# MCU.net
KiCad netlist of a schematic drawn in Altium Designer
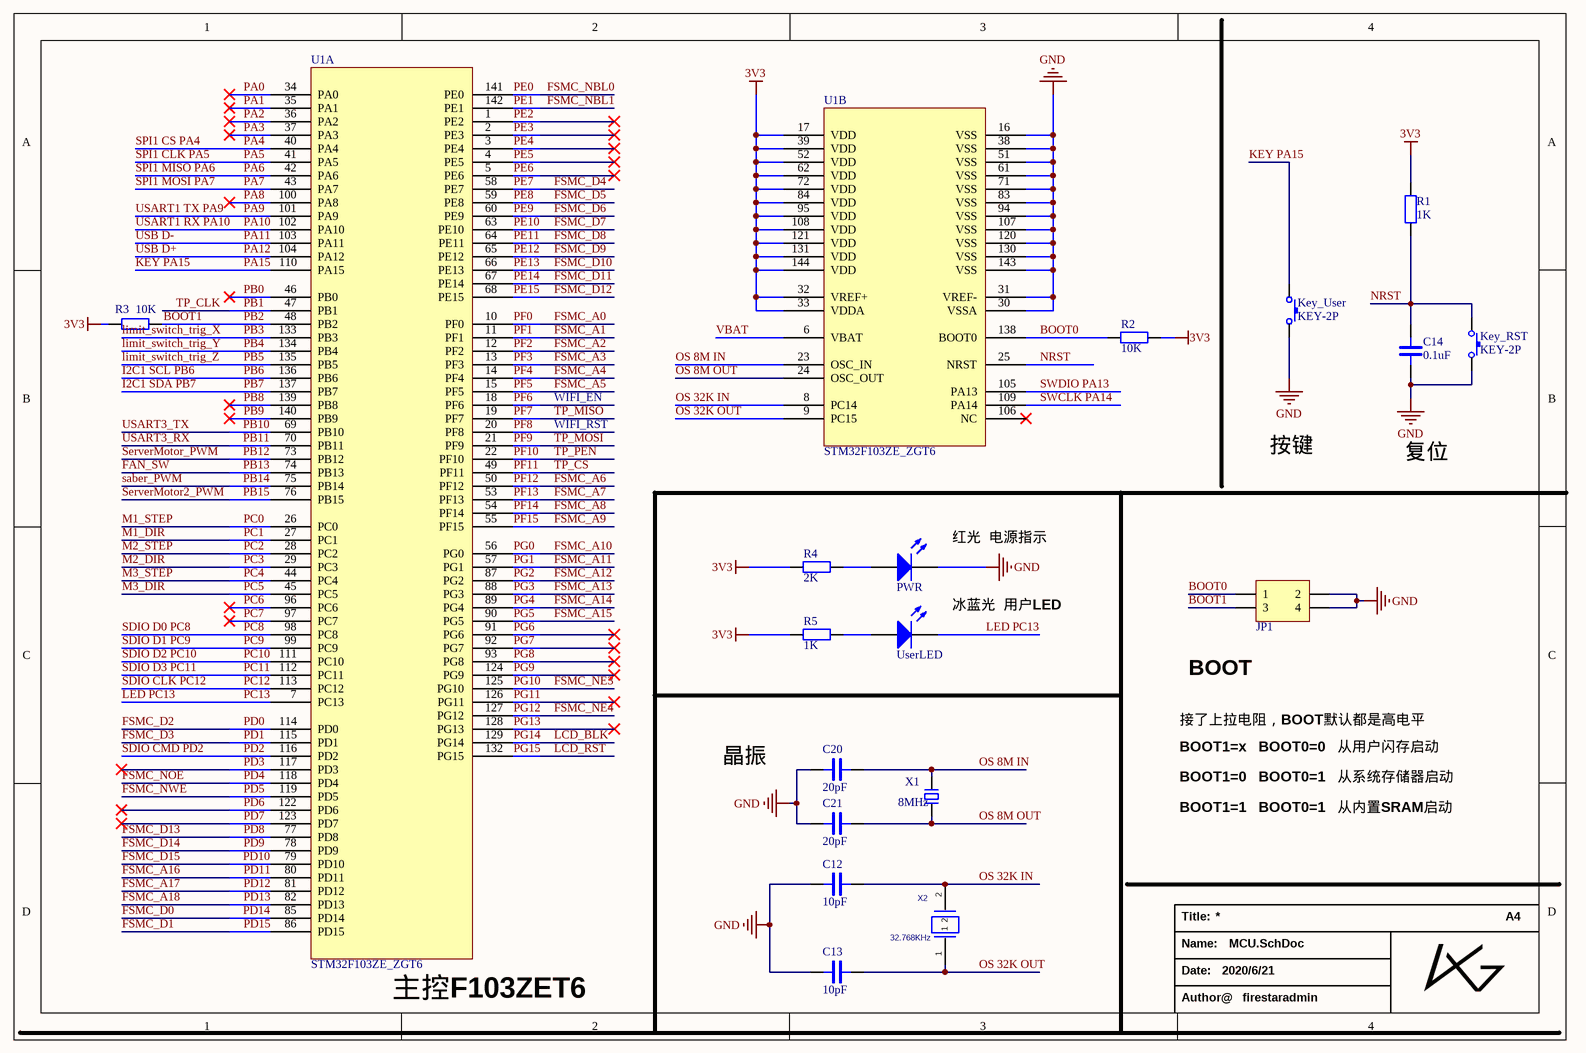
[diagram p0: MCU.SchDoc]

(export (version "E")
  (design (tool "Eeschema 10.0.6"))
  (components
    (comp (ref "C12")
      (value "10pF")
      (footprint "C 0603_M")
      (description "Capacitor")
      (libsource (lib "General") (part "CAP"))
    )
    (comp (ref "C13")
      (value "10pF")
      (footprint "C 0603_M")
      (description "Capacitor")
      (libsource (lib "General") (part "CAP"))
    )
    (comp (ref "C14")
      (value "0.1uF")
      (footprint "C 0603_M")
      (description "Capacitor")
      (libsource (lib "General") (part "CAP"))
    )
    (comp (ref "C20")
      (value "20pF")
      (footprint "C 0603_M")
      (description "Capacitor")
      (libsource (lib "General") (part "CAP"))
    )
    (comp (ref "C21")
      (value "20pF")
      (footprint "C 0603_M")
      (description "Capacitor")
      (libsource (lib "General") (part "CAP"))
    )
    (comp (ref "JP1")
      (value "Header2X2")
      (footprint "HDR2.54-LI-2x2P")
      (description "2*2P接插件")
      (fields (field (name "版权归属") "源创客"))
      (libsource (lib "4.5   - 接插件-脚距2.54") (part "Header 2X2"))
    )
    (comp (ref "Key_RST")
      (value "KEY-2P")
      (footprint "TSW SMD-3*6*2.5")
      (description "Key")
      (libsource (lib "General") (part "KEY-2P"))
    )
    (comp (ref "Key_User")
      (value "KEY-2P")
      (footprint "TSW SMD-3*6*2.5")
      (description "Key")
      (libsource (lib "General") (part "KEY-2P"))
    )
    (comp (ref "PWR")
      (value "LED")
      (footprint "LED 0603R")
      (libsource (lib "altium-import") (part "root_0_LED_"))
    )
    (comp (ref "R1")
      (value "1K")
      (footprint "R 0603_M")
      (description "Resistor")
      (libsource (lib "") (part "RES_1"))
    )
    (comp (ref "R2")
      (value "10K")
      (footprint "R 0603_M")
      (description "Resistor")
      (libsource (lib "") (part "RES_2"))
    )
    (comp (ref "R3")
      (value "10K")
      (footprint "R 0603_M")
      (description "Resistor")
      (libsource (lib "General") (part "RES"))
    )
    (comp (ref "R4")
      (value "2K")
      (footprint "R 0603_M")
      (description "Resistor")
      (libsource (lib "General") (part "RES"))
    )
    (comp (ref "R5")
      (value "1K")
      (footprint "R 0603_M")
      (description "Resistor")
      (libsource (lib "General") (part "RES"))
    )
    (comp (ref "U1")
      (value "STM32F103ZE_ZGT6")
      (footprint "TQFP144 20x20_M")
      (libsource (lib "altium-import") (part "root_0_STM32F103ZE_ZGT6_"))
    )
    (comp (ref "UserLED")
      (value "LED")
      (footprint "LED 0603B")
      (libsource (lib "altium-import") (part "root_0_LED_"))
    )
    (comp (ref "X1")
      (value "8MHz")
      (footprint "OSC 5032-2P")
      (description "2脚无源脚晶振")
      (fields (field (name "版权归属") "源创客"))
      (libsource (lib "10.1 - 保险丝-晶振") (part "XTAL-2P"))
    )
    (comp (ref "X2")
      (value "32.768KHz")
      (footprint "OSC 3215-2P")
      (description "CRYSTAL")
      (fields (field (name "Comment") "XTAL_32.768KHZ_3215"))
      (libsource (lib "altium-import") (part "root_0_XTAL_32.768KHZ_3215_"))
    )
  )
  (nets
    (net (code "1") (name "/BOOT0") (class "Default")
      (node (ref "JP1") (pin "1") (pinfunction "1_1") (pintype "passive"))
      (node (ref "R2") (pin "1") (pinfunction "1_1") (pintype "passive"))
      (node (ref "U1") (pin "138") (pinfunction "BOOT0_138") (pintype "passive"))
    )
    (net (code "2") (name "/BOOT1") (class "Default")
      (node (ref "JP1") (pin "3") (pinfunction "3_3") (pintype "passive"))
      (node (ref "R3") (pin "1") (pinfunction "1_1") (pintype "passive"))
      (node (ref "U1") (pin "48") (pinfunction "PB2_48") (pintype "passive"))
    )
    (net (code "3") (name "/FAN_SW") (class "Default")
      (node (ref "U1") (pin "74") (pinfunction "PB13_74") (pintype "passive"))
    )
    (net (code "4") (name "/FSMC_A0") (class "Default")
      (node (ref "U1") (pin "10") (pinfunction "PF0_10") (pintype "passive"))
    )
    (net (code "5") (name "/FSMC_A1") (class "Default")
      (node (ref "U1") (pin "11") (pinfunction "PF1_11") (pintype "passive"))
    )
    (net (code "6") (name "/FSMC_A2") (class "Default")
      (node (ref "U1") (pin "12") (pinfunction "PF2_12") (pintype "passive"))
    )
    (net (code "7") (name "/FSMC_A3") (class "Default")
      (node (ref "U1") (pin "13") (pinfunction "PF3_13") (pintype "passive"))
    )
    (net (code "8") (name "/FSMC_A4") (class "Default")
      (node (ref "U1") (pin "14") (pinfunction "PF4_14") (pintype "passive"))
    )
    (net (code "9") (name "/FSMC_A5") (class "Default")
      (node (ref "U1") (pin "15") (pinfunction "PF5_15") (pintype "passive"))
    )
    (net (code "10") (name "/FSMC_A6") (class "Default")
      (node (ref "U1") (pin "50") (pinfunction "PF12_50") (pintype "passive"))
    )
    (net (code "11") (name "/FSMC_A7") (class "Default")
      (node (ref "U1") (pin "53") (pinfunction "PF13_53") (pintype "passive"))
    )
    (net (code "12") (name "/FSMC_A8") (class "Default")
      (node (ref "U1") (pin "54") (pinfunction "PF14_54") (pintype "passive"))
    )
    (net (code "13") (name "/FSMC_A9") (class "Default")
      (node (ref "U1") (pin "55") (pinfunction "PF15_55") (pintype "passive"))
    )
    (net (code "14") (name "/FSMC_A10") (class "Default")
      (node (ref "U1") (pin "56") (pinfunction "PG0_56") (pintype "passive"))
    )
    (net (code "15") (name "/FSMC_A11") (class "Default")
      (node (ref "U1") (pin "57") (pinfunction "PG1_57") (pintype "passive"))
    )
    (net (code "16") (name "/FSMC_A12") (class "Default")
      (node (ref "U1") (pin "87") (pinfunction "PG2_87") (pintype "passive"))
    )
    (net (code "17") (name "/FSMC_A13") (class "Default")
      (node (ref "U1") (pin "88") (pinfunction "PG3_88") (pintype "passive"))
    )
    (net (code "18") (name "/FSMC_A14") (class "Default")
      (node (ref "U1") (pin "89") (pinfunction "PG4_89") (pintype "passive"))
    )
    (net (code "19") (name "/FSMC_A15") (class "Default")
      (node (ref "U1") (pin "90") (pinfunction "PG5_90") (pintype "passive"))
    )
    (net (code "20") (name "/FSMC_A16") (class "Default")
      (node (ref "U1") (pin "80") (pinfunction "PD11_80") (pintype "passive"))
    )
    (net (code "21") (name "/FSMC_A17") (class "Default")
      (node (ref "U1") (pin "81") (pinfunction "PD12_81") (pintype "passive"))
    )
    (net (code "22") (name "/FSMC_A18") (class "Default")
      (node (ref "U1") (pin "82") (pinfunction "PD13_82") (pintype "passive"))
    )
    (net (code "23") (name "/FSMC_D0") (class "Default")
      (node (ref "U1") (pin "85") (pinfunction "PD14_85") (pintype "passive"))
    )
    (net (code "24") (name "/FSMC_D1") (class "Default")
      (node (ref "U1") (pin "86") (pinfunction "PD15_86") (pintype "passive"))
    )
    (net (code "25") (name "/FSMC_D2") (class "Default")
      (node (ref "U1") (pin "114") (pinfunction "PD0_114") (pintype "passive"))
    )
    (net (code "26") (name "/FSMC_D3") (class "Default")
      (node (ref "U1") (pin "115") (pinfunction "PD1_115") (pintype "passive"))
    )
    (net (code "27") (name "/FSMC_D4") (class "Default")
      (node (ref "U1") (pin "58") (pinfunction "PE7_58") (pintype "passive"))
    )
    (net (code "28") (name "/FSMC_D5") (class "Default")
      (node (ref "U1") (pin "59") (pinfunction "PE8_59") (pintype "passive"))
    )
    (net (code "29") (name "/FSMC_D6") (class "Default")
      (node (ref "U1") (pin "60") (pinfunction "PE9_60") (pintype "passive"))
    )
    (net (code "30") (name "/FSMC_D7") (class "Default")
      (node (ref "U1") (pin "63") (pinfunction "PE10_63") (pintype "passive"))
    )
    (net (code "31") (name "/FSMC_D8") (class "Default")
      (node (ref "U1") (pin "64") (pinfunction "PE11_64") (pintype "passive"))
    )
    (net (code "32") (name "/FSMC_D9") (class "Default")
      (node (ref "U1") (pin "65") (pinfunction "PE12_65") (pintype "passive"))
    )
    (net (code "33") (name "/FSMC_D10") (class "Default")
      (node (ref "U1") (pin "66") (pinfunction "PE13_66") (pintype "passive"))
    )
    (net (code "34") (name "/FSMC_D11") (class "Default")
      (node (ref "U1") (pin "67") (pinfunction "PE14_67") (pintype "passive"))
    )
    (net (code "35") (name "/FSMC_D12") (class "Default")
      (node (ref "U1") (pin "68") (pinfunction "PE15_68") (pintype "passive"))
    )
    (net (code "36") (name "/FSMC_D13") (class "Default")
      (node (ref "U1") (pin "77") (pinfunction "PD8_77") (pintype "passive"))
    )
    (net (code "37") (name "/FSMC_D14") (class "Default")
      (node (ref "U1") (pin "78") (pinfunction "PD9_78") (pintype "passive"))
    )
    (net (code "38") (name "/FSMC_D15") (class "Default")
      (node (ref "U1") (pin "79") (pinfunction "PD10_79") (pintype "passive"))
    )
    (net (code "39") (name "/FSMC_NBL0") (class "Default")
      (node (ref "U1") (pin "141") (pinfunction "PE0_141") (pintype "passive"))
    )
    (net (code "40") (name "/FSMC_NBL1") (class "Default")
      (node (ref "U1") (pin "142") (pinfunction "PE1_142") (pintype "passive"))
    )
    (net (code "41") (name "/FSMC_NE3") (class "Default")
      (node (ref "U1") (pin "125") (pinfunction "PG10_125") (pintype "passive"))
    )
    (net (code "42") (name "/FSMC_NE4") (class "Default")
      (node (ref "U1") (pin "127") (pinfunction "PG12_127") (pintype "passive"))
    )
    (net (code "43") (name "/FSMC_NOE") (class "Default")
      (node (ref "U1") (pin "118") (pinfunction "PD4_118") (pintype "passive"))
    )
    (net (code "44") (name "/FSMC_NWE") (class "Default")
      (node (ref "U1") (pin "119") (pinfunction "PD5_119") (pintype "passive"))
    )
    (net (code "45") (name "/I2C1 SCL PB6") (class "Default")
      (node (ref "U1") (pin "136") (pinfunction "PB6_136") (pintype "passive"))
    )
    (net (code "46") (name "/I2C1 SDA PB7") (class "Default")
      (node (ref "U1") (pin "137") (pinfunction "PB7_137") (pintype "passive"))
    )
    (net (code "47") (name "/KEY PA15") (class "Default")
      (node (ref "Key_User") (pin "1") (pinfunction "1_1") (pintype "passive"))
      (node (ref "U1") (pin "110") (pinfunction "PA15_110") (pintype "passive"))
    )
    (net (code "48") (name "/LCD_BLK") (class "Default")
      (node (ref "U1") (pin "129") (pinfunction "PG14_129") (pintype "passive"))
    )
    (net (code "49") (name "/LCD_RST") (class "Default")
      (node (ref "U1") (pin "132") (pinfunction "PG15_132") (pintype "passive"))
    )
    (net (code "50") (name "/LED PC13") (class "Default")
      (node (ref "U1") (pin "7") (pinfunction "PC13_7") (pintype "passive"))
      (node (ref "UserLED") (pin "2") (pinfunction "K_2") (pintype "passive"))
    )
    (net (code "51") (name "/M1_DIR") (class "Default")
      (node (ref "U1") (pin "27") (pinfunction "PC1_27") (pintype "passive"))
    )
    (net (code "52") (name "/M1_STEP") (class "Default")
      (node (ref "U1") (pin "26") (pinfunction "PC0_26") (pintype "passive"))
    )
    (net (code "53") (name "/M2_DIR") (class "Default")
      (node (ref "U1") (pin "29") (pinfunction "PC3_29") (pintype "passive"))
    )
    (net (code "54") (name "/M2_STEP") (class "Default")
      (node (ref "U1") (pin "28") (pinfunction "PC2_28") (pintype "passive"))
    )
    (net (code "55") (name "/M3_DIR") (class "Default")
      (node (ref "U1") (pin "45") (pinfunction "PC5_45") (pintype "passive"))
    )
    (net (code "56") (name "/M3_STEP") (class "Default")
      (node (ref "U1") (pin "44") (pinfunction "PC4_44") (pintype "passive"))
    )
    (net (code "57") (name "/NRST") (class "Default")
      (node (ref "C14") (pin "2") (pinfunction "2_2") (pintype "passive"))
      (node (ref "Key_RST") (pin "1") (pinfunction "1_1") (pintype "passive"))
      (node (ref "R1") (pin "2") (pinfunction "2_2") (pintype "passive"))
      (node (ref "U1") (pin "25") (pinfunction "NRST_25") (pintype "passive"))
    )
    (net (code "58") (name "/OS 8M IN") (class "Default")
      (node (ref "C20") (pin "1") (pinfunction "1_1") (pintype "passive"))
      (node (ref "U1") (pin "23") (pinfunction "OSC_IN_23") (pintype "passive"))
      (node (ref "X1") (pin "1") (pinfunction "1_1") (pintype "passive"))
    )
    (net (code "59") (name "/OS 8M OUT") (class "Default")
      (node (ref "C21") (pin "1") (pinfunction "1_1") (pintype "passive"))
      (node (ref "U1") (pin "24") (pinfunction "OSC_OUT_24") (pintype "passive"))
      (node (ref "X1") (pin "2") (pinfunction "2_2") (pintype "passive"))
    )
    (net (code "60") (name "/OS 32K IN") (class "Default")
      (node (ref "C12") (pin "1") (pinfunction "1_1") (pintype "passive"))
      (node (ref "U1") (pin "8") (pinfunction "PC14_8") (pintype "passive"))
      (node (ref "X2") (pin "2") (pinfunction "2_2") (pintype "passive"))
    )
    (net (code "61") (name "/OS 32K OUT") (class "Default")
      (node (ref "C13") (pin "1") (pinfunction "1_1") (pintype "passive"))
      (node (ref "U1") (pin "9") (pinfunction "PC15_9") (pintype "passive"))
      (node (ref "X2") (pin "1") (pinfunction "1_1") (pintype "passive"))
    )
    (net (code "62") (name "/PA0") (class "Default")
      (node (ref "U1") (pin "34") (pinfunction "PA0_34") (pintype "passive+no_connect"))
    )
    (net (code "63") (name "/PA1") (class "Default")
      (node (ref "U1") (pin "35") (pinfunction "PA1_35") (pintype "passive+no_connect"))
    )
    (net (code "64") (name "/PA2") (class "Default")
      (node (ref "U1") (pin "36") (pinfunction "PA2_36") (pintype "passive+no_connect"))
    )
    (net (code "65") (name "/PA3") (class "Default")
      (node (ref "U1") (pin "37") (pinfunction "PA3_37") (pintype "passive+no_connect"))
    )
    (net (code "66") (name "/PA4") (class "Default")
      (node (ref "U1") (pin "40") (pinfunction "PA4_40") (pintype "passive"))
    )
    (net (code "67") (name "/PA5") (class "Default")
      (node (ref "U1") (pin "41") (pinfunction "PA5_41") (pintype "passive"))
    )
    (net (code "68") (name "/PA6") (class "Default")
      (node (ref "U1") (pin "42") (pinfunction "PA6_42") (pintype "passive"))
    )
    (net (code "69") (name "/PA7") (class "Default")
      (node (ref "U1") (pin "43") (pinfunction "PA7_43") (pintype "passive"))
    )
    (net (code "70") (name "/PA8") (class "Default")
      (node (ref "U1") (pin "100") (pinfunction "PA8_100") (pintype "passive+no_connect"))
    )
    (net (code "71") (name "/PA9") (class "Default")
      (node (ref "U1") (pin "101") (pinfunction "PA9_101") (pintype "passive"))
    )
    (net (code "72") (name "/PA10") (class "Default")
      (node (ref "U1") (pin "102") (pinfunction "PA10_102") (pintype "passive"))
    )
    (net (code "73") (name "/PA11") (class "Default")
      (node (ref "U1") (pin "103") (pinfunction "PA11_103") (pintype "passive"))
    )
    (net (code "74") (name "/PA12") (class "Default")
      (node (ref "U1") (pin "104") (pinfunction "PA12_104") (pintype "passive"))
    )
    (net (code "75") (name "/PB0") (class "Default")
      (node (ref "U1") (pin "46") (pinfunction "PB0_46") (pintype "passive+no_connect"))
    )
    (net (code "76") (name "/PB1") (class "Default")
      (node (ref "U1") (pin "47") (pinfunction "PB1_47") (pintype "passive"))
    )
    (net (code "77") (name "/PB3") (class "Default")
      (node (ref "U1") (pin "133") (pinfunction "PB3_133") (pintype "passive"))
    )
    (net (code "78") (name "/PB4") (class "Default")
      (node (ref "U1") (pin "134") (pinfunction "PB4_134") (pintype "passive"))
    )
    (net (code "79") (name "/PB5") (class "Default")
      (node (ref "U1") (pin "135") (pinfunction "PB5_135") (pintype "passive"))
    )
    (net (code "80") (name "/PB8") (class "Default")
      (node (ref "U1") (pin "139") (pinfunction "PB8_139") (pintype "passive+no_connect"))
    )
    (net (code "81") (name "/PB9") (class "Default")
      (node (ref "U1") (pin "140") (pinfunction "PB9_140") (pintype "passive+no_connect"))
    )
    (net (code "82") (name "/PB10") (class "Default")
      (node (ref "U1") (pin "69") (pinfunction "PB10_69") (pintype "passive"))
    )
    (net (code "83") (name "/PB11") (class "Default")
      (node (ref "U1") (pin "70") (pinfunction "PB11_70") (pintype "passive"))
    )
    (net (code "84") (name "/PB12") (class "Default")
      (node (ref "U1") (pin "73") (pinfunction "PB12_73") (pintype "passive"))
    )
    (net (code "85") (name "/PB14") (class "Default")
      (node (ref "U1") (pin "75") (pinfunction "PB14_75") (pintype "passive"))
    )
    (net (code "86") (name "/PB15") (class "Default")
      (node (ref "U1") (pin "76") (pinfunction "PB15_76") (pintype "passive"))
    )
    (net (code "87") (name "/PC6") (class "Default")
      (node (ref "U1") (pin "96") (pinfunction "PC6_96") (pintype "passive+no_connect"))
    )
    (net (code "88") (name "/PC7") (class "Default")
      (node (ref "U1") (pin "97") (pinfunction "PC7_97") (pintype "passive+no_connect"))
    )
    (net (code "89") (name "/PC8") (class "Default")
      (node (ref "U1") (pin "98") (pinfunction "PC8_98") (pintype "passive"))
    )
    (net (code "90") (name "/PC9") (class "Default")
      (node (ref "U1") (pin "99") (pinfunction "PC9_99") (pintype "passive"))
    )
    (net (code "91") (name "/PC10") (class "Default")
      (node (ref "U1") (pin "111") (pinfunction "PC10_111") (pintype "passive"))
    )
    (net (code "92") (name "/PC11") (class "Default")
      (node (ref "U1") (pin "112") (pinfunction "PC11_112") (pintype "passive"))
    )
    (net (code "93") (name "/PC12") (class "Default")
      (node (ref "U1") (pin "113") (pinfunction "PC12_113") (pintype "passive"))
    )
    (net (code "94") (name "/PD2") (class "Default")
      (node (ref "U1") (pin "116") (pinfunction "PD2_116") (pintype "passive"))
    )
    (net (code "95") (name "/PD3") (class "Default")
      (node (ref "U1") (pin "117") (pinfunction "PD3_117") (pintype "passive+no_connect"))
    )
    (net (code "96") (name "/PD6") (class "Default")
      (node (ref "U1") (pin "122") (pinfunction "PD6_122") (pintype "passive+no_connect"))
    )
    (net (code "97") (name "/PD7") (class "Default")
      (node (ref "U1") (pin "123") (pinfunction "PD7_123") (pintype "passive+no_connect"))
    )
    (net (code "98") (name "/PE2") (class "Default")
      (node (ref "U1") (pin "1") (pinfunction "PE2_1") (pintype "passive+no_connect"))
    )
    (net (code "99") (name "/PE3") (class "Default")
      (node (ref "U1") (pin "2") (pinfunction "PE3_2") (pintype "passive+no_connect"))
    )
    (net (code "100") (name "/PE4") (class "Default")
      (node (ref "U1") (pin "3") (pinfunction "PE4_3") (pintype "passive+no_connect"))
    )
    (net (code "101") (name "/PE5") (class "Default")
      (node (ref "U1") (pin "4") (pinfunction "PE5_4") (pintype "passive+no_connect"))
    )
    (net (code "102") (name "/PE6") (class "Default")
      (node (ref "U1") (pin "5") (pinfunction "PE6_5") (pintype "passive+no_connect"))
    )
    (net (code "103") (name "/PF6") (class "Default")
      (node (ref "U1") (pin "18") (pinfunction "PF6_18") (pintype "passive"))
    )
    (net (code "104") (name "/PF7") (class "Default")
      (node (ref "U1") (pin "19") (pinfunction "PF7_19") (pintype "passive"))
    )
    (net (code "105") (name "/PF8") (class "Default")
      (node (ref "U1") (pin "20") (pinfunction "PF8_20") (pintype "passive"))
    )
    (net (code "106") (name "/PF9") (class "Default")
      (node (ref "U1") (pin "21") (pinfunction "PF9_21") (pintype "passive"))
    )
    (net (code "107") (name "/PF10") (class "Default")
      (node (ref "U1") (pin "22") (pinfunction "PF10_22") (pintype "passive"))
    )
    (net (code "108") (name "/PF11") (class "Default")
      (node (ref "U1") (pin "49") (pinfunction "PF11_49") (pintype "passive"))
    )
    (net (code "109") (name "/PG6") (class "Default")
      (node (ref "U1") (pin "91") (pinfunction "PG6_91") (pintype "passive+no_connect"))
    )
    (net (code "110") (name "/PG7") (class "Default")
      (node (ref "U1") (pin "92") (pinfunction "PG7_92") (pintype "passive+no_connect"))
    )
    (net (code "111") (name "/PG8") (class "Default")
      (node (ref "U1") (pin "93") (pinfunction "PG8_93") (pintype "passive+no_connect"))
    )
    (net (code "112") (name "/PG9") (class "Default")
      (node (ref "U1") (pin "124") (pinfunction "PG9_124") (pintype "passive+no_connect"))
    )
    (net (code "113") (name "/PG11") (class "Default")
      (node (ref "U1") (pin "126") (pinfunction "PG11_126") (pintype "passive+no_connect"))
    )
    (net (code "114") (name "/PG13") (class "Default")
      (node (ref "U1") (pin "128") (pinfunction "PG13_128") (pintype "passive+no_connect"))
    )
    (net (code "115") (name "/SWCLK PA14") (class "Default")
      (node (ref "U1") (pin "109") (pinfunction "PA14_109") (pintype "passive"))
    )
    (net (code "116") (name "/SWDIO PA13") (class "Default")
      (node (ref "U1") (pin "105") (pinfunction "PA13_105") (pintype "passive"))
    )
    (net (code "117") (name "/VBAT") (class "Default")
      (node (ref "U1") (pin "6") (pinfunction "VBAT_6") (pintype "passive"))
    )
    (net (code "118") (name "3V3") (class "Default")
      (node (ref "R1") (pin "1") (pinfunction "1_1") (pintype "passive"))
      (node (ref "R2") (pin "2") (pinfunction "2_2") (pintype "passive"))
      (node (ref "R3") (pin "2") (pinfunction "2_2") (pintype "passive"))
      (node (ref "R4") (pin "2") (pinfunction "2_2") (pintype "passive"))
      (node (ref "R5") (pin "2") (pinfunction "2_2") (pintype "passive"))
      (node (ref "U1") (pin "108") (pinfunction "VDD_108") (pintype "passive"))
      (node (ref "U1") (pin "121") (pinfunction "VDD_121") (pintype "passive"))
      (node (ref "U1") (pin "131") (pinfunction "VDD_131") (pintype "passive"))
      (node (ref "U1") (pin "144") (pinfunction "VDD_144") (pintype "passive"))
      (node (ref "U1") (pin "17") (pinfunction "VDD_17") (pintype "passive"))
      (node (ref "U1") (pin "32") (pinfunction "VREF+_32") (pintype "passive"))
      (node (ref "U1") (pin "33") (pinfunction "VDDA_33") (pintype "passive"))
      (node (ref "U1") (pin "39") (pinfunction "VDD_39") (pintype "passive"))
      (node (ref "U1") (pin "52") (pinfunction "VDD_52") (pintype "passive"))
      (node (ref "U1") (pin "62") (pinfunction "VDD_62") (pintype "passive"))
      (node (ref "U1") (pin "72") (pinfunction "VDD_72") (pintype "passive"))
      (node (ref "U1") (pin "84") (pinfunction "VDD_84") (pintype "passive"))
      (node (ref "U1") (pin "95") (pinfunction "VDD_95") (pintype "passive"))
    )
    (net (code "119") (name "GND") (class "Default")
      (node (ref "C12") (pin "2") (pinfunction "2_2") (pintype "passive"))
      (node (ref "C13") (pin "2") (pinfunction "2_2") (pintype "passive"))
      (node (ref "C14") (pin "1") (pinfunction "1_1") (pintype "passive"))
      (node (ref "C20") (pin "2") (pinfunction "2_2") (pintype "passive"))
      (node (ref "C21") (pin "2") (pinfunction "2_2") (pintype "passive"))
      (node (ref "JP1") (pin "2") (pinfunction "2_2") (pintype "passive"))
      (node (ref "JP1") (pin "4") (pinfunction "4_4") (pintype "passive"))
      (node (ref "Key_RST") (pin "2") (pinfunction "2_2") (pintype "passive"))
      (node (ref "Key_User") (pin "2") (pinfunction "2_2") (pintype "passive"))
      (node (ref "PWR") (pin "2") (pinfunction "K_2") (pintype "passive"))
      (node (ref "U1") (pin "107") (pinfunction "VSS_107") (pintype "passive"))
      (node (ref "U1") (pin "120") (pinfunction "VSS_120") (pintype "passive"))
      (node (ref "U1") (pin "130") (pinfunction "VSS_130") (pintype "passive"))
      (node (ref "U1") (pin "143") (pinfunction "VSS_143") (pintype "passive"))
      (node (ref "U1") (pin "16") (pinfunction "VSS_16") (pintype "passive"))
      (node (ref "U1") (pin "30") (pinfunction "VSSA_30") (pintype "passive"))
      (node (ref "U1") (pin "31") (pinfunction "VREF-_31") (pintype "passive"))
      (node (ref "U1") (pin "38") (pinfunction "VSS_38") (pintype "passive"))
      (node (ref "U1") (pin "51") (pinfunction "VSS_51") (pintype "passive"))
      (node (ref "U1") (pin "61") (pinfunction "VSS_61") (pintype "passive"))
      (node (ref "U1") (pin "71") (pinfunction "VSS_71") (pintype "passive"))
      (node (ref "U1") (pin "83") (pinfunction "VSS_83") (pintype "passive"))
      (node (ref "U1") (pin "94") (pinfunction "VSS_94") (pintype "passive"))
    )
    (net (code "120") (name "Net-(PWR-A)") (class "Default")
      (node (ref "PWR") (pin "1") (pinfunction "A_1") (pintype "passive"))
      (node (ref "R4") (pin "1") (pinfunction "1_1") (pintype "passive"))
    )
    (net (code "121") (name "Net-(UserLED-A)") (class "Default")
      (node (ref "R5") (pin "1") (pinfunction "1_1") (pintype "passive"))
      (node (ref "UserLED") (pin "1") (pinfunction "A_1") (pintype "passive"))
    )
    (net (code "122") (name "unconnected-(U1B-NC-Pad106)") (class "Default")
      (node (ref "U1") (pin "106") (pinfunction "NC_106") (pintype "passive+no_connect"))
    )
  )
)
